# SEAx_connector.net
KiCad netlist of a schematic drawn in Altium Designer
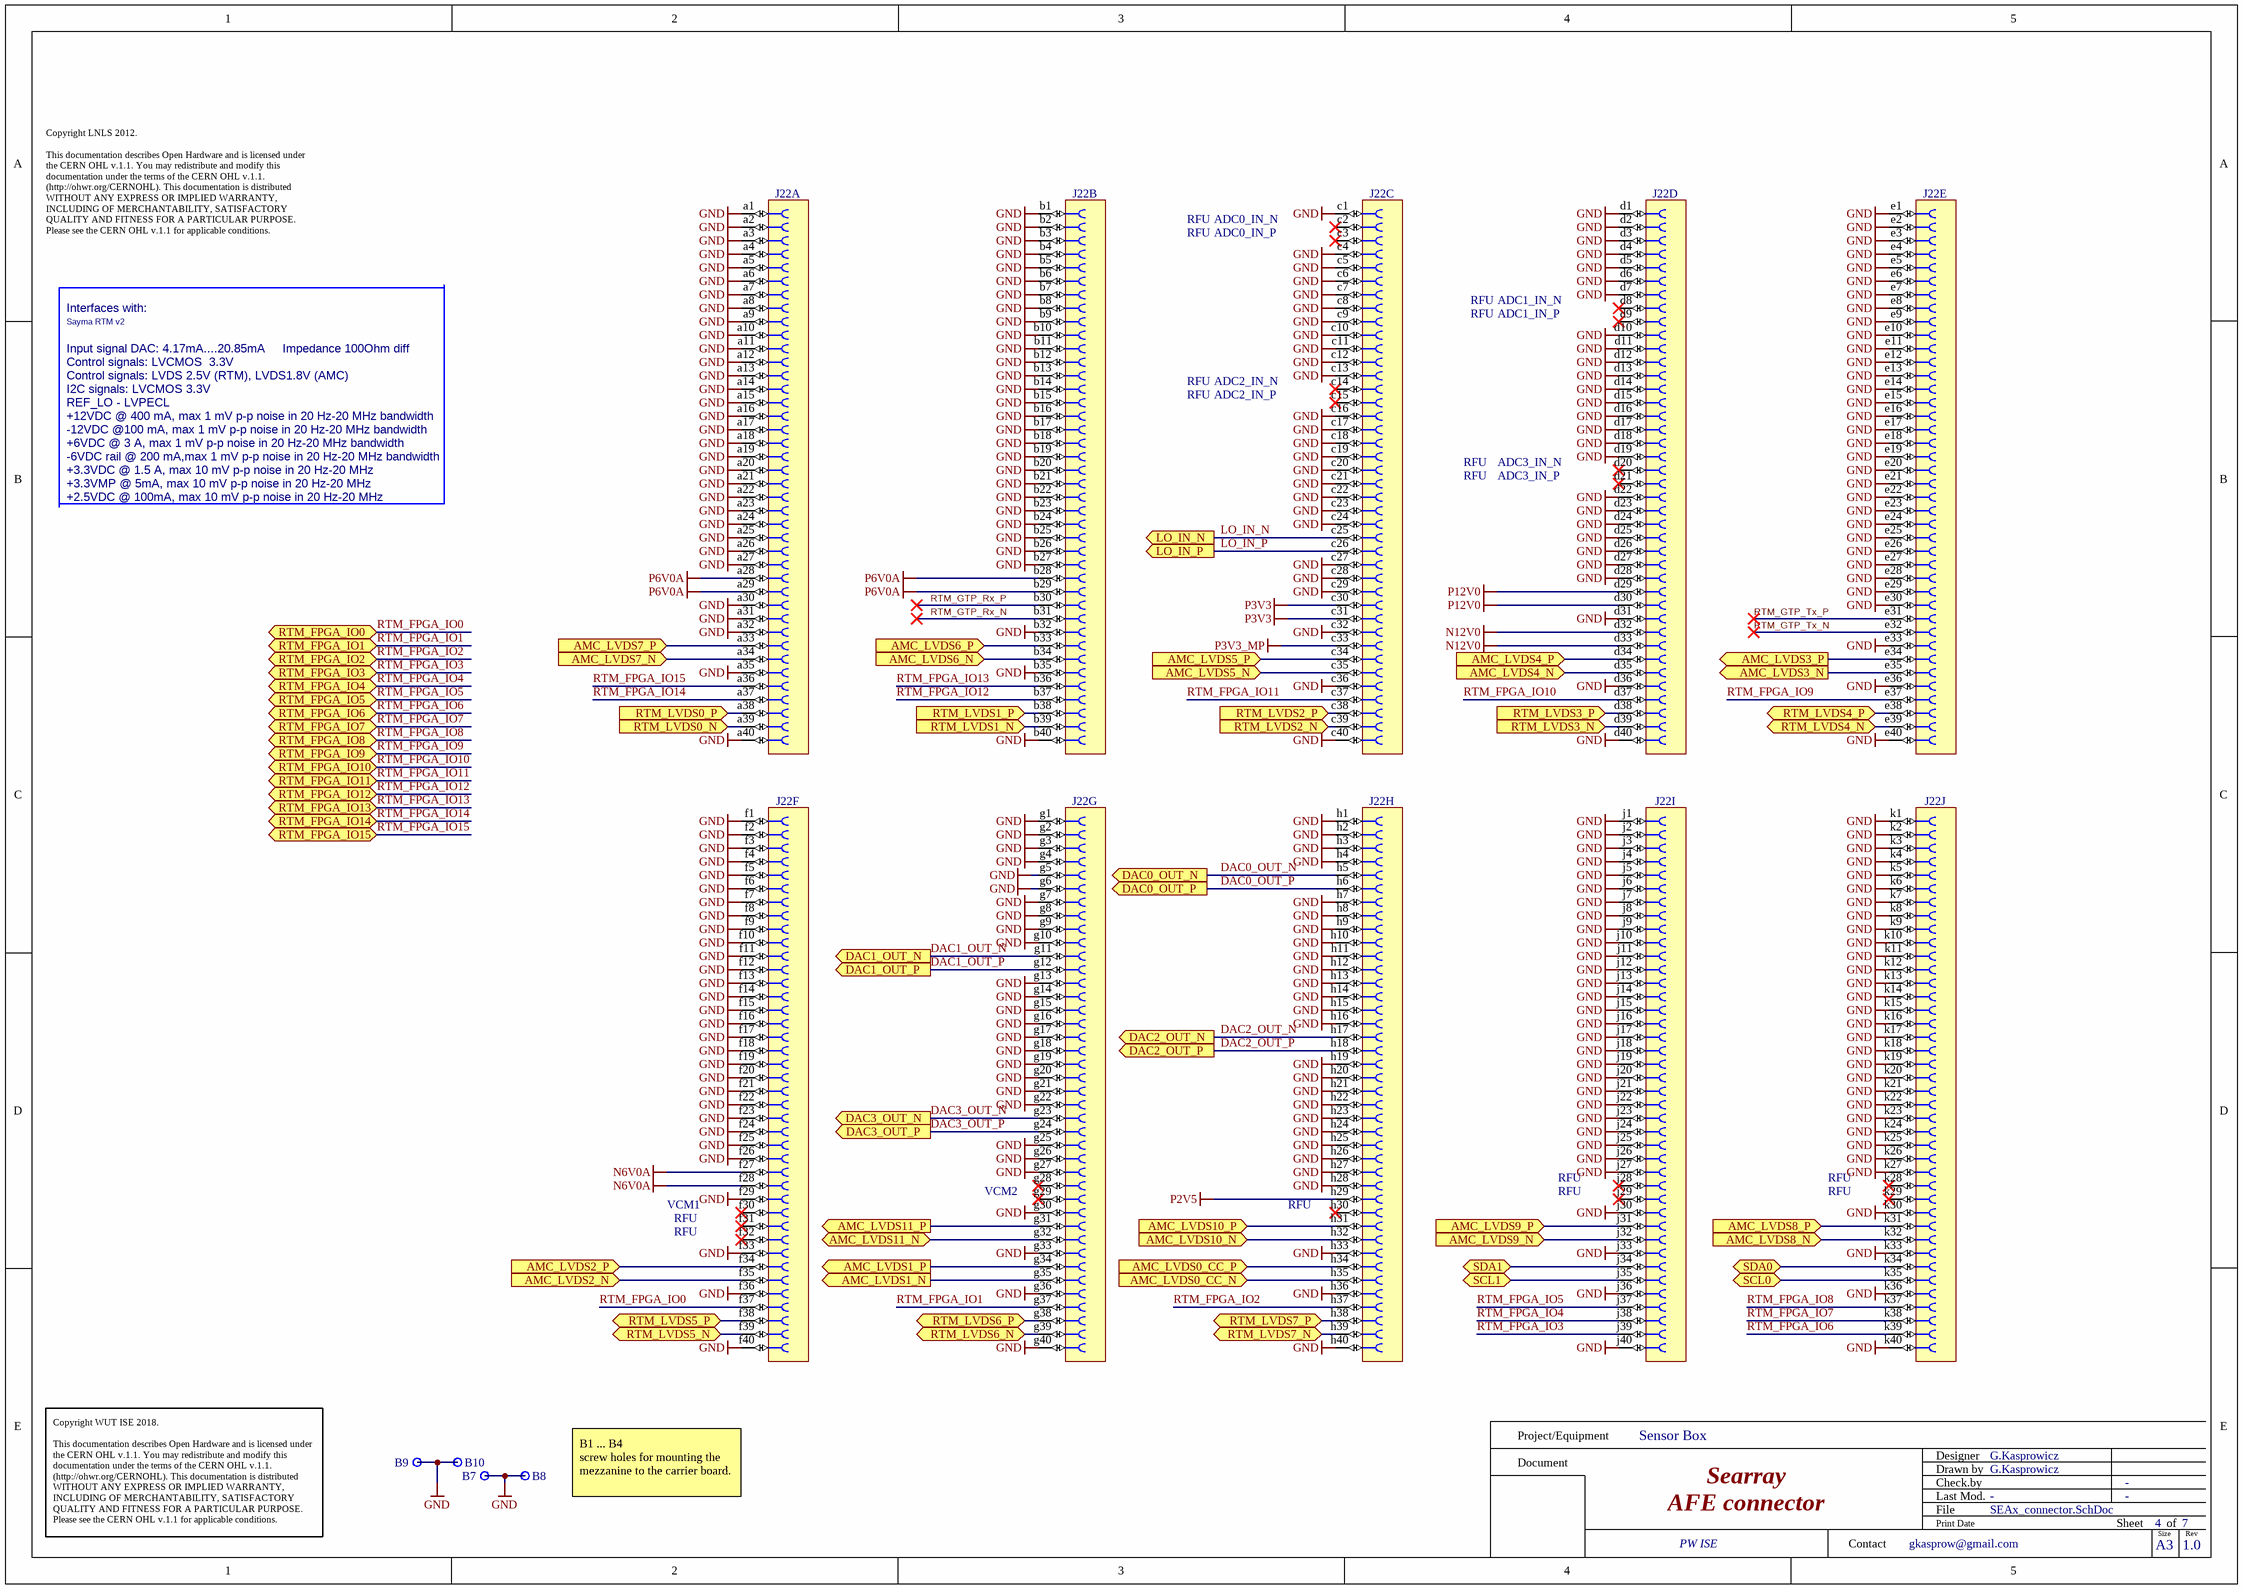
[diagram p0: SEAx_connector.SchDoc]

(export (version "E")
  (design (tool "Eeschema 10.0.6"))
  (components
    (comp (ref "B7")
      (value "Plated Hole")
      (footprint "MTG270_500")
      (description "Single Terminal Socket")
      (fields (field (name "PART NUMBER") "PLATED_HOLE2.7_PAD5.0") (field (name "AUTHOR") "CERN DEM JMW"))
      (libsource (lib "Eletro-mechanical") (part "Single Terminal Socket"))
    )
    (comp (ref "B8")
      (value "Plated Hole")
      (footprint "MTG270_500")
      (description "Single Terminal Socket")
      (fields (field (name "PART NUMBER") "PLATED_HOLE2.7_PAD5.0") (field (name "AUTHOR") "CERN DEM JMW"))
      (libsource (lib "Eletro-mechanical") (part "Single Terminal Socket"))
    )
    (comp (ref "B9")
      (value "Plated Hole")
      (footprint "MTG270_500")
      (description "Single Terminal Socket")
      (fields (field (name "PART NUMBER") "PLATED_HOLE2.7_PAD5.0") (field (name "AUTHOR") "CERN DEM JMW"))
      (libsource (lib "Eletro-mechanical") (part "Single Terminal Socket"))
    )
    (comp (ref "B10")
      (value "Plated Hole")
      (footprint "MTG270_500")
      (description "Single Terminal Socket")
      (fields (field (name "PART NUMBER") "PLATED_HOLE2.7_PAD5.0") (field (name "AUTHOR") "CERN DEM JMW"))
      (libsource (lib "Eletro-mechanical") (part "Single Terminal Socket"))
    )
    (comp (ref "J22")
      (value "VITA 57")
      (footprint "SAMTEC_ASP-134486-01")
      (description "Connector VITA 57, 400 Female contacts in 10 row abcdefghj")
      (fields
        (field (name "PART NUMBER") "SAMTEC_ASP-134486-01")
        (field (name "MANUFACTURER") "SAMTEC")
        (field (name "AUTHOR") "CERN DEM JLC")
      )
      (libsource (lib "Connectors") (part "Connector VITA 57 400 Female (abcdefghjk)"))
    )
  )
  (nets
    (net (code "1") (name "/AMC_LVDS0_CC_N") (class "Default")
      (node (ref "J22") (pin "h35") (pinfunction "h35_h35") (pintype "bidirectional"))
    )
    (net (code "2") (name "/AMC_LVDS0_CC_P") (class "Default")
      (node (ref "J22") (pin "h34") (pinfunction "h34_h34") (pintype "bidirectional"))
    )
    (net (code "3") (name "/AMC_LVDS1_N") (class "Default")
      (node (ref "J22") (pin "g35") (pinfunction "g35_g35") (pintype "bidirectional"))
    )
    (net (code "4") (name "/AMC_LVDS1_P") (class "Default")
      (node (ref "J22") (pin "g34") (pinfunction "g34_g34") (pintype "bidirectional"))
    )
    (net (code "5") (name "/AMC_LVDS2_N") (class "Default")
      (node (ref "J22") (pin "f35") (pinfunction "f35_f35") (pintype "bidirectional"))
    )
    (net (code "6") (name "/AMC_LVDS2_P") (class "Default")
      (node (ref "J22") (pin "f34") (pinfunction "f34_f34") (pintype "bidirectional"))
    )
    (net (code "7") (name "/AMC_LVDS3_N") (class "Default")
      (node (ref "J22") (pin "e35") (pinfunction "e35_e35") (pintype "bidirectional"))
    )
    (net (code "8") (name "/AMC_LVDS3_P") (class "Default")
      (node (ref "J22") (pin "e34") (pinfunction "e34_e34") (pintype "bidirectional"))
    )
    (net (code "9") (name "/AMC_LVDS4_N") (class "Default")
      (node (ref "J22") (pin "d35") (pinfunction "d35_d35") (pintype "bidirectional"))
    )
    (net (code "10") (name "/AMC_LVDS4_P") (class "Default")
      (node (ref "J22") (pin "d34") (pinfunction "d34_d34") (pintype "bidirectional"))
    )
    (net (code "11") (name "/AMC_LVDS5_N") (class "Default")
      (node (ref "J22") (pin "c35") (pinfunction "c35_c35") (pintype "bidirectional"))
    )
    (net (code "12") (name "/AMC_LVDS5_P") (class "Default")
      (node (ref "J22") (pin "c34") (pinfunction "c34_c34") (pintype "bidirectional"))
    )
    (net (code "13") (name "/AMC_LVDS6_N") (class "Default")
      (node (ref "J22") (pin "b34") (pinfunction "b34_b34") (pintype "bidirectional"))
    )
    (net (code "14") (name "/AMC_LVDS6_P") (class "Default")
      (node (ref "J22") (pin "b33") (pinfunction "b33_b33") (pintype "bidirectional"))
    )
    (net (code "15") (name "/AMC_LVDS7_N") (class "Default")
      (node (ref "J22") (pin "a34") (pinfunction "a34_a34") (pintype "bidirectional"))
    )
    (net (code "16") (name "/AMC_LVDS7_P") (class "Default")
      (node (ref "J22") (pin "a33") (pinfunction "a33_a33") (pintype "bidirectional"))
    )
    (net (code "17") (name "/AMC_LVDS8_N") (class "Default")
      (node (ref "J22") (pin "k32") (pinfunction "k32_k32") (pintype "bidirectional"))
    )
    (net (code "18") (name "/AMC_LVDS8_P") (class "Default")
      (node (ref "J22") (pin "k31") (pinfunction "k31_k31") (pintype "bidirectional"))
    )
    (net (code "19") (name "/AMC_LVDS9_N") (class "Default")
      (node (ref "J22") (pin "j32") (pinfunction "j32_j32") (pintype "bidirectional"))
    )
    (net (code "20") (name "/AMC_LVDS9_P") (class "Default")
      (node (ref "J22") (pin "j31") (pinfunction "j31_j31") (pintype "bidirectional"))
    )
    (net (code "21") (name "/AMC_LVDS10_N") (class "Default")
      (node (ref "J22") (pin "h32") (pinfunction "h32_h32") (pintype "bidirectional"))
    )
    (net (code "22") (name "/AMC_LVDS10_P") (class "Default")
      (node (ref "J22") (pin "h31") (pinfunction "h31_h31") (pintype "bidirectional"))
    )
    (net (code "23") (name "/AMC_LVDS11_N") (class "Default")
      (node (ref "J22") (pin "g32") (pinfunction "g32_g32") (pintype "bidirectional"))
    )
    (net (code "24") (name "/AMC_LVDS11_P") (class "Default")
      (node (ref "J22") (pin "g31") (pinfunction "g31_g31") (pintype "bidirectional"))
    )
    (net (code "25") (name "/DAC0_OUT_N") (class "Default")
      (node (ref "J22") (pin "h5") (pinfunction "h5_h5") (pintype "bidirectional"))
    )
    (net (code "26") (name "/DAC0_OUT_P") (class "Default")
      (node (ref "J22") (pin "h6") (pinfunction "h6_h6") (pintype "bidirectional"))
    )
    (net (code "27") (name "/DAC1_OUT_N") (class "Default")
      (node (ref "J22") (pin "g11") (pinfunction "g11_g11") (pintype "bidirectional"))
    )
    (net (code "28") (name "/DAC1_OUT_P") (class "Default")
      (node (ref "J22") (pin "g12") (pinfunction "g12_g12") (pintype "bidirectional"))
    )
    (net (code "29") (name "/DAC2_OUT_N") (class "Default")
      (node (ref "J22") (pin "h17") (pinfunction "h17_h17") (pintype "bidirectional"))
    )
    (net (code "30") (name "/DAC2_OUT_P") (class "Default")
      (node (ref "J22") (pin "h18") (pinfunction "h18_h18") (pintype "bidirectional"))
    )
    (net (code "31") (name "/DAC3_OUT_N") (class "Default")
      (node (ref "J22") (pin "g23") (pinfunction "g23_g23") (pintype "bidirectional"))
    )
    (net (code "32") (name "/DAC3_OUT_P") (class "Default")
      (node (ref "J22") (pin "g24") (pinfunction "g24_g24") (pintype "bidirectional"))
    )
    (net (code "33") (name "/LO_IN_N") (class "Default")
      (node (ref "J22") (pin "c25") (pinfunction "c25_c25") (pintype "bidirectional"))
    )
    (net (code "34") (name "/LO_IN_P") (class "Default")
      (node (ref "J22") (pin "c26") (pinfunction "c26_c26") (pintype "bidirectional"))
    )
    (net (code "35") (name "/RTM_FPGA_IO0") (class "Default")
      (node (ref "J22") (pin "f37") (pinfunction "f37_f37") (pintype "bidirectional"))
    )
    (net (code "36") (name "/RTM_FPGA_IO1") (class "Default")
      (node (ref "J22") (pin "g37") (pinfunction "g37_g37") (pintype "bidirectional"))
    )
    (net (code "37") (name "/RTM_FPGA_IO2") (class "Default")
      (node (ref "J22") (pin "h37") (pinfunction "h37_h37") (pintype "bidirectional"))
    )
    (net (code "38") (name "/RTM_FPGA_IO3") (class "Default")
      (node (ref "J22") (pin "j39") (pinfunction "j39_j39") (pintype "bidirectional"))
    )
    (net (code "39") (name "/RTM_FPGA_IO4") (class "Default")
      (node (ref "J22") (pin "j38") (pinfunction "j38_j38") (pintype "bidirectional"))
    )
    (net (code "40") (name "/RTM_FPGA_IO5") (class "Default")
      (node (ref "J22") (pin "j37") (pinfunction "j37_j37") (pintype "bidirectional"))
    )
    (net (code "41") (name "/RTM_FPGA_IO6") (class "Default")
      (node (ref "J22") (pin "k39") (pinfunction "k39_k39") (pintype "bidirectional"))
    )
    (net (code "42") (name "/RTM_FPGA_IO7") (class "Default")
      (node (ref "J22") (pin "k38") (pinfunction "k38_k38") (pintype "bidirectional"))
    )
    (net (code "43") (name "/RTM_FPGA_IO8") (class "Default")
      (node (ref "J22") (pin "k37") (pinfunction "k37_k37") (pintype "bidirectional"))
    )
    (net (code "44") (name "/RTM_FPGA_IO9") (class "Default")
      (node (ref "J22") (pin "e37") (pinfunction "e37_e37") (pintype "bidirectional"))
    )
    (net (code "45") (name "/RTM_FPGA_IO10") (class "Default")
      (node (ref "J22") (pin "d37") (pinfunction "d37_d37") (pintype "bidirectional"))
    )
    (net (code "46") (name "/RTM_FPGA_IO11") (class "Default")
      (node (ref "J22") (pin "c37") (pinfunction "c37_c37") (pintype "bidirectional"))
    )
    (net (code "47") (name "/RTM_FPGA_IO12") (class "Default")
      (node (ref "J22") (pin "b37") (pinfunction "b37_b37") (pintype "bidirectional"))
    )
    (net (code "48") (name "/RTM_FPGA_IO13") (class "Default")
      (node (ref "J22") (pin "b36") (pinfunction "b36_b36") (pintype "bidirectional"))
    )
    (net (code "49") (name "/RTM_FPGA_IO14") (class "Default")
      (node (ref "J22") (pin "a37") (pinfunction "a37_a37") (pintype "bidirectional"))
    )
    (net (code "50") (name "/RTM_FPGA_IO15") (class "Default")
      (node (ref "J22") (pin "a36") (pinfunction "a36_a36") (pintype "bidirectional"))
    )
    (net (code "51") (name "/RTM_GTP_Rx_N") (class "Default")
      (node (ref "J22") (pin "b31") (pinfunction "b31_b31") (pintype "bidirectional+no_connect"))
    )
    (net (code "52") (name "/RTM_GTP_Rx_P") (class "Default")
      (node (ref "J22") (pin "b30") (pinfunction "b30_b30") (pintype "bidirectional+no_connect"))
    )
    (net (code "53") (name "/RTM_GTP_Tx_N") (class "Default")
      (node (ref "J22") (pin "e32") (pinfunction "e32_e32") (pintype "bidirectional+no_connect"))
    )
    (net (code "54") (name "/RTM_GTP_Tx_P") (class "Default")
      (node (ref "J22") (pin "e31") (pinfunction "e31_e31") (pintype "bidirectional+no_connect"))
    )
    (net (code "55") (name "/RTM_LVDS0_N") (class "Default")
      (node (ref "J22") (pin "a39") (pinfunction "a39_a39") (pintype "bidirectional"))
    )
    (net (code "56") (name "/RTM_LVDS0_P") (class "Default")
      (node (ref "J22") (pin "a38") (pinfunction "a38_a38") (pintype "bidirectional"))
    )
    (net (code "57") (name "/RTM_LVDS1_N") (class "Default")
      (node (ref "J22") (pin "b39") (pinfunction "b39_b39") (pintype "bidirectional"))
    )
    (net (code "58") (name "/RTM_LVDS1_P") (class "Default")
      (node (ref "J22") (pin "b38") (pinfunction "b38_b38") (pintype "bidirectional"))
    )
    (net (code "59") (name "/RTM_LVDS2_N") (class "Default")
      (node (ref "J22") (pin "c39") (pinfunction "c39_c39") (pintype "bidirectional"))
    )
    (net (code "60") (name "/RTM_LVDS2_P") (class "Default")
      (node (ref "J22") (pin "c38") (pinfunction "c38_c38") (pintype "bidirectional"))
    )
    (net (code "61") (name "/RTM_LVDS3_N") (class "Default")
      (node (ref "J22") (pin "d39") (pinfunction "d39_d39") (pintype "bidirectional"))
    )
    (net (code "62") (name "/RTM_LVDS3_P") (class "Default")
      (node (ref "J22") (pin "d38") (pinfunction "d38_d38") (pintype "bidirectional"))
    )
    (net (code "63") (name "/RTM_LVDS4_N") (class "Default")
      (node (ref "J22") (pin "e39") (pinfunction "e39_e39") (pintype "bidirectional"))
    )
    (net (code "64") (name "/RTM_LVDS4_P") (class "Default")
      (node (ref "J22") (pin "e38") (pinfunction "e38_e38") (pintype "bidirectional"))
    )
    (net (code "65") (name "/RTM_LVDS5_N") (class "Default")
      (node (ref "J22") (pin "f39") (pinfunction "f39_f39") (pintype "bidirectional"))
    )
    (net (code "66") (name "/RTM_LVDS5_P") (class "Default")
      (node (ref "J22") (pin "f38") (pinfunction "f38_f38") (pintype "bidirectional"))
    )
    (net (code "67") (name "/RTM_LVDS6_N") (class "Default")
      (node (ref "J22") (pin "g39") (pinfunction "g39_g39") (pintype "bidirectional"))
    )
    (net (code "68") (name "/RTM_LVDS6_P") (class "Default")
      (node (ref "J22") (pin "g38") (pinfunction "g38_g38") (pintype "bidirectional"))
    )
    (net (code "69") (name "/RTM_LVDS7_N") (class "Default")
      (node (ref "J22") (pin "h39") (pinfunction "h39_h39") (pintype "bidirectional"))
    )
    (net (code "70") (name "/RTM_LVDS7_P") (class "Default")
      (node (ref "J22") (pin "h38") (pinfunction "h38_h38") (pintype "bidirectional"))
    )
    (net (code "71") (name "/SCL0") (class "Default")
      (node (ref "J22") (pin "k35") (pinfunction "k35_k35") (pintype "bidirectional"))
    )
    (net (code "72") (name "/SCL1") (class "Default")
      (node (ref "J22") (pin "j35") (pinfunction "j35_j35") (pintype "bidirectional"))
    )
    (net (code "73") (name "/SDA0") (class "Default")
      (node (ref "J22") (pin "k34") (pinfunction "k34_k34") (pintype "bidirectional"))
    )
    (net (code "74") (name "/SDA1") (class "Default")
      (node (ref "J22") (pin "j34") (pinfunction "j34_j34") (pintype "bidirectional"))
    )
    (net (code "75") (name "GND") (class "Default")
      (node (ref "B10") (pin "1") (pinfunction "1_1") (pintype "bidirectional"))
      (node (ref "B7") (pin "1") (pinfunction "1_1") (pintype "bidirectional"))
      (node (ref "B8") (pin "1") (pinfunction "1_1") (pintype "bidirectional"))
      (node (ref "B9") (pin "1") (pinfunction "1_1") (pintype "bidirectional"))
      (node (ref "J22") (pin "a1") (pinfunction "a1_a1") (pintype "bidirectional"))
      (node (ref "J22") (pin "a10") (pinfunction "a10_a10") (pintype "bidirectional"))
      (node (ref "J22") (pin "a11") (pinfunction "a11_a11") (pintype "bidirectional"))
      (node (ref "J22") (pin "a12") (pinfunction "a12_a12") (pintype "bidirectional"))
      (node (ref "J22") (pin "a13") (pinfunction "a13_a13") (pintype "bidirectional"))
      (node (ref "J22") (pin "a14") (pinfunction "a14_a14") (pintype "bidirectional"))
      (node (ref "J22") (pin "a15") (pinfunction "a15_a15") (pintype "bidirectional"))
      (node (ref "J22") (pin "a16") (pinfunction "a16_a16") (pintype "bidirectional"))
      (node (ref "J22") (pin "a17") (pinfunction "a17_a17") (pintype "bidirectional"))
      (node (ref "J22") (pin "a18") (pinfunction "a18_a18") (pintype "bidirectional"))
      (node (ref "J22") (pin "a19") (pinfunction "a19_a19") (pintype "bidirectional"))
      (node (ref "J22") (pin "a2") (pinfunction "a2_a2") (pintype "bidirectional"))
      (node (ref "J22") (pin "a20") (pinfunction "a20_a20") (pintype "bidirectional"))
      (node (ref "J22") (pin "a21") (pinfunction "a21_a21") (pintype "bidirectional"))
      (node (ref "J22") (pin "a22") (pinfunction "a22_a22") (pintype "bidirectional"))
      (node (ref "J22") (pin "a23") (pinfunction "a23_a23") (pintype "bidirectional"))
      (node (ref "J22") (pin "a24") (pinfunction "a24_a24") (pintype "bidirectional"))
      (node (ref "J22") (pin "a25") (pinfunction "a25_a25") (pintype "bidirectional"))
      (node (ref "J22") (pin "a26") (pinfunction "a26_a26") (pintype "bidirectional"))
      (node (ref "J22") (pin "a27") (pinfunction "a27_a27") (pintype "bidirectional"))
      (node (ref "J22") (pin "a3") (pinfunction "a3_a3") (pintype "bidirectional"))
      (node (ref "J22") (pin "a30") (pinfunction "a30_a30") (pintype "bidirectional"))
      (node (ref "J22") (pin "a31") (pinfunction "a31_a31") (pintype "bidirectional"))
      (node (ref "J22") (pin "a32") (pinfunction "a32_a32") (pintype "bidirectional"))
      (node (ref "J22") (pin "a35") (pinfunction "a35_a35") (pintype "bidirectional"))
      (node (ref "J22") (pin "a4") (pinfunction "a4_a4") (pintype "bidirectional"))
      (node (ref "J22") (pin "a40") (pinfunction "a40_a40") (pintype "bidirectional"))
      (node (ref "J22") (pin "a5") (pinfunction "a5_a5") (pintype "bidirectional"))
      (node (ref "J22") (pin "a6") (pinfunction "a6_a6") (pintype "bidirectional"))
      (node (ref "J22") (pin "a7") (pinfunction "a7_a7") (pintype "bidirectional"))
      (node (ref "J22") (pin "a8") (pinfunction "a8_a8") (pintype "bidirectional"))
      (node (ref "J22") (pin "a9") (pinfunction "a9_a9") (pintype "bidirectional"))
      (node (ref "J22") (pin "b1") (pinfunction "b1_b1") (pintype "bidirectional"))
      (node (ref "J22") (pin "b10") (pinfunction "b10_b10") (pintype "bidirectional"))
      (node (ref "J22") (pin "b11") (pinfunction "b11_b11") (pintype "bidirectional"))
      (node (ref "J22") (pin "b12") (pinfunction "b12_b12") (pintype "bidirectional"))
      (node (ref "J22") (pin "b13") (pinfunction "b13_b13") (pintype "bidirectional"))
      (node (ref "J22") (pin "b14") (pinfunction "b14_b14") (pintype "bidirectional"))
      (node (ref "J22") (pin "b15") (pinfunction "b15_b15") (pintype "bidirectional"))
      (node (ref "J22") (pin "b16") (pinfunction "b16_b16") (pintype "bidirectional"))
      (node (ref "J22") (pin "b17") (pinfunction "b17_b17") (pintype "bidirectional"))
      (node (ref "J22") (pin "b18") (pinfunction "b18_b18") (pintype "bidirectional"))
      (node (ref "J22") (pin "b19") (pinfunction "b19_b19") (pintype "bidirectional"))
      (node (ref "J22") (pin "b2") (pinfunction "b2_b2") (pintype "bidirectional"))
      (node (ref "J22") (pin "b20") (pinfunction "b20_b20") (pintype "bidirectional"))
      (node (ref "J22") (pin "b21") (pinfunction "b21_b21") (pintype "bidirectional"))
      (node (ref "J22") (pin "b22") (pinfunction "b22_b22") (pintype "bidirectional"))
      (node (ref "J22") (pin "b23") (pinfunction "b23_b23") (pintype "bidirectional"))
      (node (ref "J22") (pin "b24") (pinfunction "b24_b24") (pintype "bidirectional"))
      (node (ref "J22") (pin "b25") (pinfunction "b25_b25") (pintype "bidirectional"))
      (node (ref "J22") (pin "b26") (pinfunction "b26_b26") (pintype "bidirectional"))
      (node (ref "J22") (pin "b27") (pinfunction "b27_b27") (pintype "bidirectional"))
      (node (ref "J22") (pin "b3") (pinfunction "b3_b3") (pintype "bidirectional"))
      (node (ref "J22") (pin "b32") (pinfunction "b32_b32") (pintype "bidirectional"))
      (node (ref "J22") (pin "b35") (pinfunction "b35_b35") (pintype "bidirectional"))
      (node (ref "J22") (pin "b4") (pinfunction "b4_b4") (pintype "bidirectional"))
      (node (ref "J22") (pin "b40") (pinfunction "b40_b40") (pintype "bidirectional"))
      (node (ref "J22") (pin "b5") (pinfunction "b5_b5") (pintype "bidirectional"))
      (node (ref "J22") (pin "b6") (pinfunction "b6_b6") (pintype "bidirectional"))
      (node (ref "J22") (pin "b7") (pinfunction "b7_b7") (pintype "bidirectional"))
      (node (ref "J22") (pin "b8") (pinfunction "b8_b8") (pintype "bidirectional"))
      (node (ref "J22") (pin "b9") (pinfunction "b9_b9") (pintype "bidirectional"))
      (node (ref "J22") (pin "c1") (pinfunction "c1_c1") (pintype "bidirectional"))
      (node (ref "J22") (pin "c10") (pinfunction "c10_c10") (pintype "bidirectional"))
      (node (ref "J22") (pin "c11") (pinfunction "c11_c11") (pintype "bidirectional"))
      (node (ref "J22") (pin "c12") (pinfunction "c12_c12") (pintype "bidirectional"))
      (node (ref "J22") (pin "c13") (pinfunction "c13_c13") (pintype "bidirectional"))
      (node (ref "J22") (pin "c16") (pinfunction "c16_c16") (pintype "bidirectional"))
      (node (ref "J22") (pin "c17") (pinfunction "c17_c17") (pintype "bidirectional"))
      (node (ref "J22") (pin "c18") (pinfunction "c18_c18") (pintype "bidirectional"))
      (node (ref "J22") (pin "c19") (pinfunction "c19_c19") (pintype "bidirectional"))
      (node (ref "J22") (pin "c20") (pinfunction "c20_c20") (pintype "bidirectional"))
      (node (ref "J22") (pin "c21") (pinfunction "c21_c21") (pintype "bidirectional"))
      (node (ref "J22") (pin "c22") (pinfunction "c22_c22") (pintype "bidirectional"))
      (node (ref "J22") (pin "c23") (pinfunction "c23_c23") (pintype "bidirectional"))
      (node (ref "J22") (pin "c24") (pinfunction "c24_c24") (pintype "bidirectional"))
      (node (ref "J22") (pin "c27") (pinfunction "c27_c27") (pintype "bidirectional"))
      (node (ref "J22") (pin "c28") (pinfunction "c28_c28") (pintype "bidirectional"))
      (node (ref "J22") (pin "c29") (pinfunction "c29_c29") (pintype "bidirectional"))
      (node (ref "J22") (pin "c32") (pinfunction "c32_c32") (pintype "bidirectional"))
      (node (ref "J22") (pin "c36") (pinfunction "c36_c36") (pintype "bidirectional"))
      (node (ref "J22") (pin "c4") (pinfunction "c4_c4") (pintype "bidirectional"))
      (node (ref "J22") (pin "c40") (pinfunction "c40_c40") (pintype "bidirectional"))
      (node (ref "J22") (pin "c5") (pinfunction "c5_c5") (pintype "bidirectional"))
      (node (ref "J22") (pin "c6") (pinfunction "c6_c6") (pintype "bidirectional"))
      (node (ref "J22") (pin "c7") (pinfunction "c7_c7") (pintype "bidirectional"))
      (node (ref "J22") (pin "c8") (pinfunction "c8_c8") (pintype "bidirectional"))
      (node (ref "J22") (pin "c9") (pinfunction "c9_c9") (pintype "bidirectional"))
      (node (ref "J22") (pin "d1") (pinfunction "d1_d1") (pintype "bidirectional"))
      (node (ref "J22") (pin "d10") (pinfunction "d10_d10") (pintype "bidirectional"))
      (node (ref "J22") (pin "d11") (pinfunction "d11_d11") (pintype "bidirectional"))
      (node (ref "J22") (pin "d12") (pinfunction "d12_d12") (pintype "bidirectional"))
      (node (ref "J22") (pin "d13") (pinfunction "d13_d13") (pintype "bidirectional"))
      (node (ref "J22") (pin "d14") (pinfunction "d14_d14") (pintype "bidirectional"))
      (node (ref "J22") (pin "d15") (pinfunction "d15_d15") (pintype "bidirectional"))
      (node (ref "J22") (pin "d16") (pinfunction "d16_d16") (pintype "bidirectional"))
      (node (ref "J22") (pin "d17") (pinfunction "d17_d17") (pintype "bidirectional"))
      (node (ref "J22") (pin "d18") (pinfunction "d18_d18") (pintype "bidirectional"))
      (node (ref "J22") (pin "d19") (pinfunction "d19_d19") (pintype "bidirectional"))
      (node (ref "J22") (pin "d2") (pinfunction "d2_d2") (pintype "bidirectional"))
      (node (ref "J22") (pin "d22") (pinfunction "d22_d22") (pintype "bidirectional"))
      (node (ref "J22") (pin "d23") (pinfunction "d23_d23") (pintype "bidirectional"))
      (node (ref "J22") (pin "d24") (pinfunction "d24_d24") (pintype "bidirectional"))
      (node (ref "J22") (pin "d25") (pinfunction "d25_d25") (pintype "bidirectional"))
      (node (ref "J22") (pin "d26") (pinfunction "d26_d26") (pintype "bidirectional"))
      (node (ref "J22") (pin "d27") (pinfunction "d27_d27") (pintype "bidirectional"))
      (node (ref "J22") (pin "d28") (pinfunction "d28_d28") (pintype "bidirectional"))
      (node (ref "J22") (pin "d3") (pinfunction "d3_d3") (pintype "bidirectional"))
      (node (ref "J22") (pin "d31") (pinfunction "d31_d31") (pintype "bidirectional"))
      (node (ref "J22") (pin "d36") (pinfunction "d36_d36") (pintype "bidirectional"))
      (node (ref "J22") (pin "d4") (pinfunction "d4_d4") (pintype "bidirectional"))
      (node (ref "J22") (pin "d40") (pinfunction "d40_d40") (pintype "bidirectional"))
      (node (ref "J22") (pin "d5") (pinfunction "d5_d5") (pintype "bidirectional"))
      (node (ref "J22") (pin "d6") (pinfunction "d6_d6") (pintype "bidirectional"))
      (node (ref "J22") (pin "d7") (pinfunction "d7_d7") (pintype "bidirectional"))
      (node (ref "J22") (pin "e1") (pinfunction "e1_e1") (pintype "bidirectional"))
      (node (ref "J22") (pin "e10") (pinfunction "e10_e10") (pintype "bidirectional"))
      (node (ref "J22") (pin "e11") (pinfunction "e11_e11") (pintype "bidirectional"))
      (node (ref "J22") (pin "e12") (pinfunction "e12_e12") (pintype "bidirectional"))
      (node (ref "J22") (pin "e13") (pinfunction "e13_e13") (pintype "bidirectional"))
      (node (ref "J22") (pin "e14") (pinfunction "e14_e14") (pintype "bidirectional"))
      (node (ref "J22") (pin "e15") (pinfunction "e15_e15") (pintype "bidirectional"))
      (node (ref "J22") (pin "e16") (pinfunction "e16_e16") (pintype "bidirectional"))
      (node (ref "J22") (pin "e17") (pinfunction "e17_e17") (pintype "bidirectional"))
      (node (ref "J22") (pin "e18") (pinfunction "e18_e18") (pintype "bidirectional"))
      (node (ref "J22") (pin "e19") (pinfunction "e19_e19") (pintype "bidirectional"))
      (node (ref "J22") (pin "e2") (pinfunction "e2_e2") (pintype "bidirectional"))
      (node (ref "J22") (pin "e20") (pinfunction "e20_e20") (pintype "bidirectional"))
      (node (ref "J22") (pin "e21") (pinfunction "e21_e21") (pintype "bidirectional"))
      (node (ref "J22") (pin "e22") (pinfunction "e22_e22") (pintype "bidirectional"))
      (node (ref "J22") (pin "e23") (pinfunction "e23_e23") (pintype "bidirectional"))
      (node (ref "J22") (pin "e24") (pinfunction "e24_e24") (pintype "bidirectional"))
      (node (ref "J22") (pin "e25") (pinfunction "e25_e25") (pintype "bidirectional"))
      (node (ref "J22") (pin "e26") (pinfunction "e26_e26") (pintype "bidirectional"))
      (node (ref "J22") (pin "e27") (pinfunction "e27_e27") (pintype "bidirectional"))
      (node (ref "J22") (pin "e28") (pinfunction "e28_e28") (pintype "bidirectional"))
      (node (ref "J22") (pin "e29") (pinfunction "e29_e29") (pintype "bidirectional"))
      (node (ref "J22") (pin "e3") (pinfunction "e3_e3") (pintype "bidirectional"))
      (node (ref "J22") (pin "e30") (pinfunction "e30_e30") (pintype "bidirectional"))
      (node (ref "J22") (pin "e33") (pinfunction "e33_e33") (pintype "bidirectional"))
      (node (ref "J22") (pin "e36") (pinfunction "e36_e36") (pintype "bidirectional"))
      (node (ref "J22") (pin "e4") (pinfunction "e4_e4") (pintype "bidirectional"))
      (node (ref "J22") (pin "e40") (pinfunction "e40_e40") (pintype "bidirectional"))
      (node (ref "J22") (pin "e5") (pinfunction "e5_e5") (pintype "bidirectional"))
      (node (ref "J22") (pin "e6") (pinfunction "e6_e6") (pintype "bidirectional"))
      (node (ref "J22") (pin "e7") (pinfunction "e7_e7") (pintype "bidirectional"))
      (node (ref "J22") (pin "e8") (pinfunction "e8_e8") (pintype "bidirectional"))
      (node (ref "J22") (pin "e9") (pinfunction "e9_e9") (pintype "bidirectional"))
      (node (ref "J22") (pin "f1") (pinfunction "f1_f1") (pintype "bidirectional"))
      (node (ref "J22") (pin "f10") (pinfunction "f10_f10") (pintype "bidirectional"))
      (node (ref "J22") (pin "f11") (pinfunction "f11_f11") (pintype "bidirectional"))
      (node (ref "J22") (pin "f12") (pinfunction "f12_f12") (pintype "bidirectional"))
      (node (ref "J22") (pin "f13") (pinfunction "f13_f13") (pintype "bidirectional"))
      (node (ref "J22") (pin "f14") (pinfunction "f14_f14") (pintype "bidirectional"))
      (node (ref "J22") (pin "f15") (pinfunction "f15_f15") (pintype "bidirectional"))
      (node (ref "J22") (pin "f16") (pinfunction "f16_f16") (pintype "bidirectional"))
      (node (ref "J22") (pin "f17") (pinfunction "f17_f17") (pintype "bidirectional"))
      (node (ref "J22") (pin "f18") (pinfunction "f18_f18") (pintype "bidirectional"))
      (node (ref "J22") (pin "f19") (pinfunction "f19_f19") (pintype "bidirectional"))
      (node (ref "J22") (pin "f2") (pinfunction "f2_f2") (pintype "bidirectional"))
      (node (ref "J22") (pin "f20") (pinfunction "f20_f20") (pintype "bidirectional"))
      (node (ref "J22") (pin "f21") (pinfunction "f21_f21") (pintype "bidirectional"))
      (node (ref "J22") (pin "f22") (pinfunction "f22_f22") (pintype "bidirectional"))
      (node (ref "J22") (pin "f23") (pinfunction "f23_f23") (pintype "bidirectional"))
      (node (ref "J22") (pin "f24") (pinfunction "f24_f24") (pintype "bidirectional"))
      (node (ref "J22") (pin "f25") (pinfunction "f25_f25") (pintype "bidirectional"))
      (node (ref "J22") (pin "f26") (pinfunction "f26_f26") (pintype "bidirectional"))
      (node (ref "J22") (pin "f29") (pinfunction "f29_f29") (pintype "bidirectional"))
      (node (ref "J22") (pin "f3") (pinfunction "f3_f3") (pintype "bidirectional"))
      (node (ref "J22") (pin "f33") (pinfunction "f33_f33") (pintype "bidirectional"))
      (node (ref "J22") (pin "f36") (pinfunction "f36_f36") (pintype "bidirectional"))
      (node (ref "J22") (pin "f4") (pinfunction "f4_f4") (pintype "bidirectional"))
      (node (ref "J22") (pin "f40") (pinfunction "f40_f40") (pintype "bidirectional"))
      (node (ref "J22") (pin "f5") (pinfunction "f5_f5") (pintype "bidirectional"))
      (node (ref "J22") (pin "f6") (pinfunction "f6_f6") (pintype "bidirectional"))
      (node (ref "J22") (pin "f7") (pinfunction "f7_f7") (pintype "bidirectional"))
      (node (ref "J22") (pin "f8") (pinfunction "f8_f8") (pintype "bidirectional"))
      (node (ref "J22") (pin "f9") (pinfunction "f9_f9") (pintype "bidirectional"))
      (node (ref "J22") (pin "g1") (pinfunction "g1_g1") (pintype "bidirectional"))
      (node (ref "J22") (pin "g10") (pinfunction "g10_g10") (pintype "bidirectional"))
      (node (ref "J22") (pin "g13") (pinfunction "g13_g13") (pintype "bidirectional"))
      (node (ref "J22") (pin "g14") (pinfunction "g14_g14") (pintype "bidirectional"))
      (node (ref "J22") (pin "g15") (pinfunction "g15_g15") (pintype "bidirectional"))
      (node (ref "J22") (pin "g16") (pinfunction "g16_g16") (pintype "bidirectional"))
      (node (ref "J22") (pin "g17") (pinfunction "g17_g17") (pintype "bidirectional"))
      (node (ref "J22") (pin "g18") (pinfunction "g18_g18") (pintype "bidirectional"))
      (node (ref "J22") (pin "g19") (pinfunction "g19_g19") (pintype "bidirectional"))
      (node (ref "J22") (pin "g2") (pinfunction "g2_g2") (pintype "bidirectional"))
      (node (ref "J22") (pin "g20") (pinfunction "g20_g20") (pintype "bidirectional"))
      (node (ref "J22") (pin "g21") (pinfunction "g21_g21") (pintype "bidirectional"))
      (node (ref "J22") (pin "g22") (pinfunction "g22_g22") (pintype "bidirectional"))
      (node (ref "J22") (pin "g25") (pinfunction "g25_g25") (pintype "bidirectional"))
      (node (ref "J22") (pin "g26") (pinfunction "g26_g26") (pintype "bidirectional"))
      (node (ref "J22") (pin "g27") (pinfunction "g27_g27") (pintype "bidirectional"))
      (node (ref "J22") (pin "g3") (pinfunction "g3_g3") (pintype "bidirectional"))
      (node (ref "J22") (pin "g30") (pinfunction "g30_g30") (pintype "bidirectional"))
      (node (ref "J22") (pin "g33") (pinfunction "g33_g33") (pintype "bidirectional"))
      (node (ref "J22") (pin "g36") (pinfunction "g36_g36") (pintype "bidirectional"))
      (node (ref "J22") (pin "g4") (pinfunction "g4_g4") (pintype "bidirectional"))
      (node (ref "J22") (pin "g40") (pinfunction "g40_g40") (pintype "bidirectional"))
      (node (ref "J22") (pin "g5") (pinfunction "g5_g5") (pintype "bidirectional"))
      (node (ref "J22") (pin "g6") (pinfunction "g6_g6") (pintype "bidirectional"))
      (node (ref "J22") (pin "g7") (pinfunction "g7_g7") (pintype "bidirectional"))
      (node (ref "J22") (pin "g8") (pinfunction "g8_g8") (pintype "bidirectional"))
      (node (ref "J22") (pin "g9") (pinfunction "g9_g9") (pintype "bidirectional"))
      (node (ref "J22") (pin "h1") (pinfunction "h1_h1") (pintype "bidirectional"))
      (node (ref "J22") (pin "h10") (pinfunction "h10_h10") (pintype "bidirectional"))
      (node (ref "J22") (pin "h11") (pinfunction "h11_h11") (pintype "bidirectional"))
      (node (ref "J22") (pin "h12") (pinfunction "h12_h12") (pintype "bidirectional"))
      (node (ref "J22") (pin "h13") (pinfunction "h13_h13") (pintype "bidirectional"))
      (node (ref "J22") (pin "h14") (pinfunction "h14_h14") (pintype "bidirectional"))
      (node (ref "J22") (pin "h15") (pinfunction "h15_h15") (pintype "bidirectional"))
      (node (ref "J22") (pin "h16") (pinfunction "h16_h16") (pintype "bidirectional"))
      (node (ref "J22") (pin "h19") (pinfunction "h19_h19") (pintype "bidirectional"))
      (node (ref "J22") (pin "h2") (pinfunction "h2_h2") (pintype "bidirectional"))
      (node (ref "J22") (pin "h20") (pinfunction "h20_h20") (pintype "bidirectional"))
      (node (ref "J22") (pin "h21") (pinfunction "h21_h21") (pintype "bidirectional"))
      (node (ref "J22") (pin "h22") (pinfunction "h22_h22") (pintype "bidirectional"))
      (node (ref "J22") (pin "h23") (pinfunction "h23_h23") (pintype "bidirectional"))
      (node (ref "J22") (pin "h24") (pinfunction "h24_h24") (pintype "bidirectional"))
      (node (ref "J22") (pin "h25") (pinfunction "h25_h25") (pintype "bidirectional"))
      (node (ref "J22") (pin "h26") (pinfunction "h26_h26") (pintype "bidirectional"))
      (node (ref "J22") (pin "h27") (pinfunction "h27_h27") (pintype "bidirectional"))
      (node (ref "J22") (pin "h28") (pinfunction "h28_h28") (pintype "bidirectional"))
      (node (ref "J22") (pin "h3") (pinfunction "h3_h3") (pintype "bidirectional"))
      (node (ref "J22") (pin "h33") (pinfunction "h33_h33") (pintype "bidirectional"))
      (node (ref "J22") (pin "h36") (pinfunction "h36_h36") (pintype "bidirectional"))
      (node (ref "J22") (pin "h4") (pinfunction "h4_h4") (pintype "bidirectional"))
      (node (ref "J22") (pin "h40") (pinfunction "h40_h40") (pintype "bidirectional"))
      (node (ref "J22") (pin "h7") (pinfunction "h7_h7") (pintype "bidirectional"))
      (node (ref "J22") (pin "h8") (pinfunction "h8_h8") (pintype "bidirectional"))
      (node (ref "J22") (pin "h9") (pinfunction "h9_h9") (pintype "bidirectional"))
      (node (ref "J22") (pin "j1") (pinfunction "j1_j1") (pintype "bidirectional"))
      (node (ref "J22") (pin "j10") (pinfunction "j10_j10") (pintype "bidirectional"))
      (node (ref "J22") (pin "j11") (pinfunction "j11_j11") (pintype "bidirectional"))
      (node (ref "J22") (pin "j12") (pinfunction "j12_j12") (pintype "bidirectional"))
      (node (ref "J22") (pin "j13") (pinfunction "j13_j13") (pintype "bidirectional"))
      (node (ref "J22") (pin "j14") (pinfunction "j14_j14") (pintype "bidirectional"))
      (node (ref "J22") (pin "j15") (pinfunction "j15_j15") (pintype "bidirectional"))
      (node (ref "J22") (pin "j16") (pinfunction "j16_j16") (pintype "bidirectional"))
      (node (ref "J22") (pin "j17") (pinfunction "j17_j17") (pintype "bidirectional"))
      (node (ref "J22") (pin "j18") (pinfunction "j18_j18") (pintype "bidirectional"))
      (node (ref "J22") (pin "j19") (pinfunction "j19_j19") (pintype "bidirectional"))
      (node (ref "J22") (pin "j2") (pinfunction "j2_j2") (pintype "bidirectional"))
      (node (ref "J22") (pin "j20") (pinfunction "j20_j20") (pintype "bidirectional"))
      (node (ref "J22") (pin "j21") (pinfunction "j21_j21") (pintype "bidirectional"))
      (node (ref "J22") (pin "j22") (pinfunction "j22_j22") (pintype "bidirectional"))
      (node (ref "J22") (pin "j23") (pinfunction "j23_j23") (pintype "bidirectional"))
      (node (ref "J22") (pin "j24") (pinfunction "j24_j24") (pintype "bidirectional"))
      (node (ref "J22") (pin "j25") (pinfunction "j25_j25") (pintype "bidirectional"))
      (node (ref "J22") (pin "j26") (pinfunction "j26_j26") (pintype "bidirectional"))
      (node (ref "J22") (pin "j27") (pinfunction "j27_j27") (pintype "bidirectional"))
      (node (ref "J22") (pin "j3") (pinfunction "j3_j3") (pintype "bidirectional"))
      (node (ref "J22") (pin "j30") (pinfunction "j30_j30") (pintype "bidirectional"))
      (node (ref "J22") (pin "j33") (pinfunction "j33_j33") (pintype "bidirectional"))
      (node (ref "J22") (pin "j36") (pinfunction "j36_j36") (pintype "bidirectional"))
      (node (ref "J22") (pin "j4") (pinfunction "j4_j4") (pintype "bidirectional"))
      (node (ref "J22") (pin "j40") (pinfunction "j40_j40") (pintype "bidirectional"))
      (node (ref "J22") (pin "j5") (pinfunction "j5_j5") (pintype "bidirectional"))
      (node (ref "J22") (pin "j6") (pinfunction "j6_j6") (pintype "bidirectional"))
      (node (ref "J22") (pin "j7") (pinfunction "j7_j7") (pintype "bidirectional"))
      (node (ref "J22") (pin "j8") (pinfunction "j8_j8") (pintype "bidirectional"))
      (node (ref "J22") (pin "j9") (pinfunction "j9_j9") (pintype "bidirectional"))
      (node (ref "J22") (pin "k1") (pinfunction "k1_k1") (pintype "bidirectional"))
      (node (ref "J22") (pin "k10") (pinfunction "k10_k10") (pintype "bidirectional"))
      (node (ref "J22") (pin "k11") (pinfunction "k11_k11") (pintype "bidirectional"))
      (node (ref "J22") (pin "k12") (pinfunction "k12_k12") (pintype "bidirectional"))
      (node (ref "J22") (pin "k13") (pinfunction "k13_k13") (pintype "bidirectional"))
      (node (ref "J22") (pin "k14") (pinfunction "k14_k14") (pintype "bidirectional"))
      (node (ref "J22") (pin "k15") (pinfunction "k15_k15") (pintype "bidirectional"))
      (node (ref "J22") (pin "k16") (pinfunction "k16_k16") (pintype "bidirectional"))
      (node (ref "J22") (pin "k17") (pinfunction "k17_k17") (pintype "bidirectional"))
      (node (ref "J22") (pin "k18") (pinfunction "k18_k18") (pintype "bidirectional"))
      (node (ref "J22") (pin "k19") (pinfunction "k19_k19") (pintype "bidirectional"))
      (node (ref "J22") (pin "k2") (pinfunction "k2_k2") (pintype "bidirectional"))
      (node (ref "J22") (pin "k20") (pinfunction "k20_k20") (pintype "bidirectional"))
      (node (ref "J22") (pin "k21") (pinfunction "k21_k21") (pintype "bidirectional"))
      (node (ref "J22") (pin "k22") (pinfunction "k22_k22") (pintype "bidirectional"))
      (node (ref "J22") (pin "k23") (pinfunction "k23_k23") (pintype "bidirectional"))
      (node (ref "J22") (pin "k24") (pinfunction "k24_k24") (pintype "bidirectional"))
      (node (ref "J22") (pin "k25") (pinfunction "k25_k25") (pintype "bidirectional"))
      (node (ref "J22") (pin "k26") (pinfunction "k26_k26") (pintype "bidirectional"))
      (node (ref "J22") (pin "k27") (pinfunction "k27_k27") (pintype "bidirectional"))
      (node (ref "J22") (pin "k3") (pinfunction "k3_k3") (pintype "bidirectional"))
      (node (ref "J22") (pin "k30") (pinfunction "k30_k30") (pintype "bidirectional"))
      (node (ref "J22") (pin "k33") (pinfunction "k33_k33") (pintype "bidirectional"))
      (node (ref "J22") (pin "k36") (pinfunction "k36_k36") (pintype "bidirectional"))
      (node (ref "J22") (pin "k4") (pinfunction "k4_k4") (pintype "bidirectional"))
      (node (ref "J22") (pin "k40") (pinfunction "k40_k40") (pintype "bidirectional"))
      (node (ref "J22") (pin "k5") (pinfunction "k5_k5") (pintype "bidirectional"))
      (node (ref "J22") (pin "k6") (pinfunction "k6_k6") (pintype "bidirectional"))
      (node (ref "J22") (pin "k7") (pinfunction "k7_k7") (pintype "bidirectional"))
      (node (ref "J22") (pin "k8") (pinfunction "k8_k8") (pintype "bidirectional"))
      (node (ref "J22") (pin "k9") (pinfunction "k9_k9") (pintype "bidirectional"))
    )
    (net (code "76") (name "N6V0A") (class "Default")
      (node (ref "J22") (pin "f27") (pinfunction "f27_f27") (pintype "bidirectional"))
      (node (ref "J22") (pin "f28") (pinfunction "f28_f28") (pintype "bidirectional"))
    )
    (net (code "77") (name "N12V0") (class "Default")
      (node (ref "J22") (pin "d32") (pinfunction "d32_d32") (pintype "bidirectional"))
      (node (ref "J22") (pin "d33") (pinfunction "d33_d33") (pintype "bidirectional"))
    )
    (net (code "78") (name "P2V5") (class "Default")
      (node (ref "J22") (pin "h29") (pinfunction "h29_h29") (pintype "bidirectional"))
    )
    (net (code "79") (name "P3V3") (class "Default")
      (node (ref "J22") (pin "c30") (pinfunction "c30_c30") (pintype "bidirectional"))
      (node (ref "J22") (pin "c31") (pinfunction "c31_c31") (pintype "bidirectional"))
    )
    (net (code "80") (name "P3V3_MP") (class "Default")
      (node (ref "J22") (pin "c33") (pinfunction "c33_c33") (pintype "bidirectional"))
    )
    (net (code "81") (name "P6V0A") (class "Default")
      (node (ref "J22") (pin "a28") (pinfunction "a28_a28") (pintype "bidirectional"))
      (node (ref "J22") (pin "a29") (pinfunction "a29_a29") (pintype "bidirectional"))
      (node (ref "J22") (pin "b28") (pinfunction "b28_b28") (pintype "bidirectional"))
      (node (ref "J22") (pin "b29") (pinfunction "b29_b29") (pintype "bidirectional"))
    )
    (net (code "82") (name "P12V0") (class "Default")
      (node (ref "J22") (pin "d29") (pinfunction "d29_d29") (pintype "bidirectional"))
      (node (ref "J22") (pin "d30") (pinfunction "d30_d30") (pintype "bidirectional"))
    )
    (net (code "83") (name "unconnected-(J22-Padc2)") (class "Default")
      (node (ref "J22") (pin "c2") (pinfunction "c2_c2") (pintype "bidirectional+no_connect"))
    )
    (net (code "84") (name "unconnected-(J22-Padc3)") (class "Default")
      (node (ref "J22") (pin "c3") (pinfunction "c3_c3") (pintype "bidirectional+no_connect"))
    )
    (net (code "85") (name "unconnected-(J22-Padc14)") (class "Default")
      (node (ref "J22") (pin "c14") (pinfunction "c14_c14") (pintype "bidirectional+no_connect"))
    )
    (net (code "86") (name "unconnected-(J22-Padc15)") (class "Default")
      (node (ref "J22") (pin "c15") (pinfunction "c15_c15") (pintype "bidirectional+no_connect"))
    )
    (net (code "87") (name "unconnected-(J22-Padd8)") (class "Default")
      (node (ref "J22") (pin "d8") (pinfunction "d8_d8") (pintype "bidirectional+no_connect"))
    )
    (net (code "88") (name "unconnected-(J22-Padd9)") (class "Default")
      (node (ref "J22") (pin "d9") (pinfunction "d9_d9") (pintype "bidirectional+no_connect"))
    )
    (net (code "89") (name "unconnected-(J22-Padd20)") (class "Default")
      (node (ref "J22") (pin "d20") (pinfunction "d20_d20") (pintype "bidirectional+no_connect"))
    )
    (net (code "90") (name "unconnected-(J22-Padd21)") (class "Default")
      (node (ref "J22") (pin "d21") (pinfunction "d21_d21") (pintype "bidirectional+no_connect"))
    )
    (net (code "91") (name "unconnected-(J22-Padf30)") (class "Default")
      (node (ref "J22") (pin "f30") (pinfunction "f30_f30") (pintype "bidirectional+no_connect"))
    )
    (net (code "92") (name "unconnected-(J22-Padf31)") (class "Default")
      (node (ref "J22") (pin "f31") (pinfunction "f31_f31") (pintype "bidirectional+no_connect"))
    )
    (net (code "93") (name "unconnected-(J22-Padf32)") (class "Default")
      (node (ref "J22") (pin "f32") (pinfunction "f32_f32") (pintype "bidirectional+no_connect"))
    )
    (net (code "94") (name "unconnected-(J22-Padg28)") (class "Default")
      (node (ref "J22") (pin "g28") (pinfunction "g28_g28") (pintype "bidirectional+no_connect"))
    )
    (net (code "95") (name "unconnected-(J22-Padg29)") (class "Default")
      (node (ref "J22") (pin "g29") (pinfunction "g29_g29") (pintype "bidirectional+no_connect"))
    )
    (net (code "96") (name "unconnected-(J22-Padh30)") (class "Default")
      (node (ref "J22") (pin "h30") (pinfunction "h30_h30") (pintype "bidirectional+no_connect"))
    )
    (net (code "97") (name "unconnected-(J22-Padj28)") (class "Default")
      (node (ref "J22") (pin "j28") (pinfunction "j28_j28") (pintype "bidirectional+no_connect"))
    )
    (net (code "98") (name "unconnected-(J22-Padj29)") (class "Default")
      (node (ref "J22") (pin "j29") (pinfunction "j29_j29") (pintype "bidirectional+no_connect"))
    )
    (net (code "99") (name "unconnected-(J22-Padk28)") (class "Default")
      (node (ref "J22") (pin "k28") (pinfunction "k28_k28") (pintype "bidirectional+no_connect"))
    )
    (net (code "100") (name "unconnected-(J22-Padk29)") (class "Default")
      (node (ref "J22") (pin "k29") (pinfunction "k29_k29") (pintype "bidirectional+no_connect"))
    )
  )
)
